# 04_Optical_Heads.net
KiCad netlist of a schematic drawn in Altium Designer
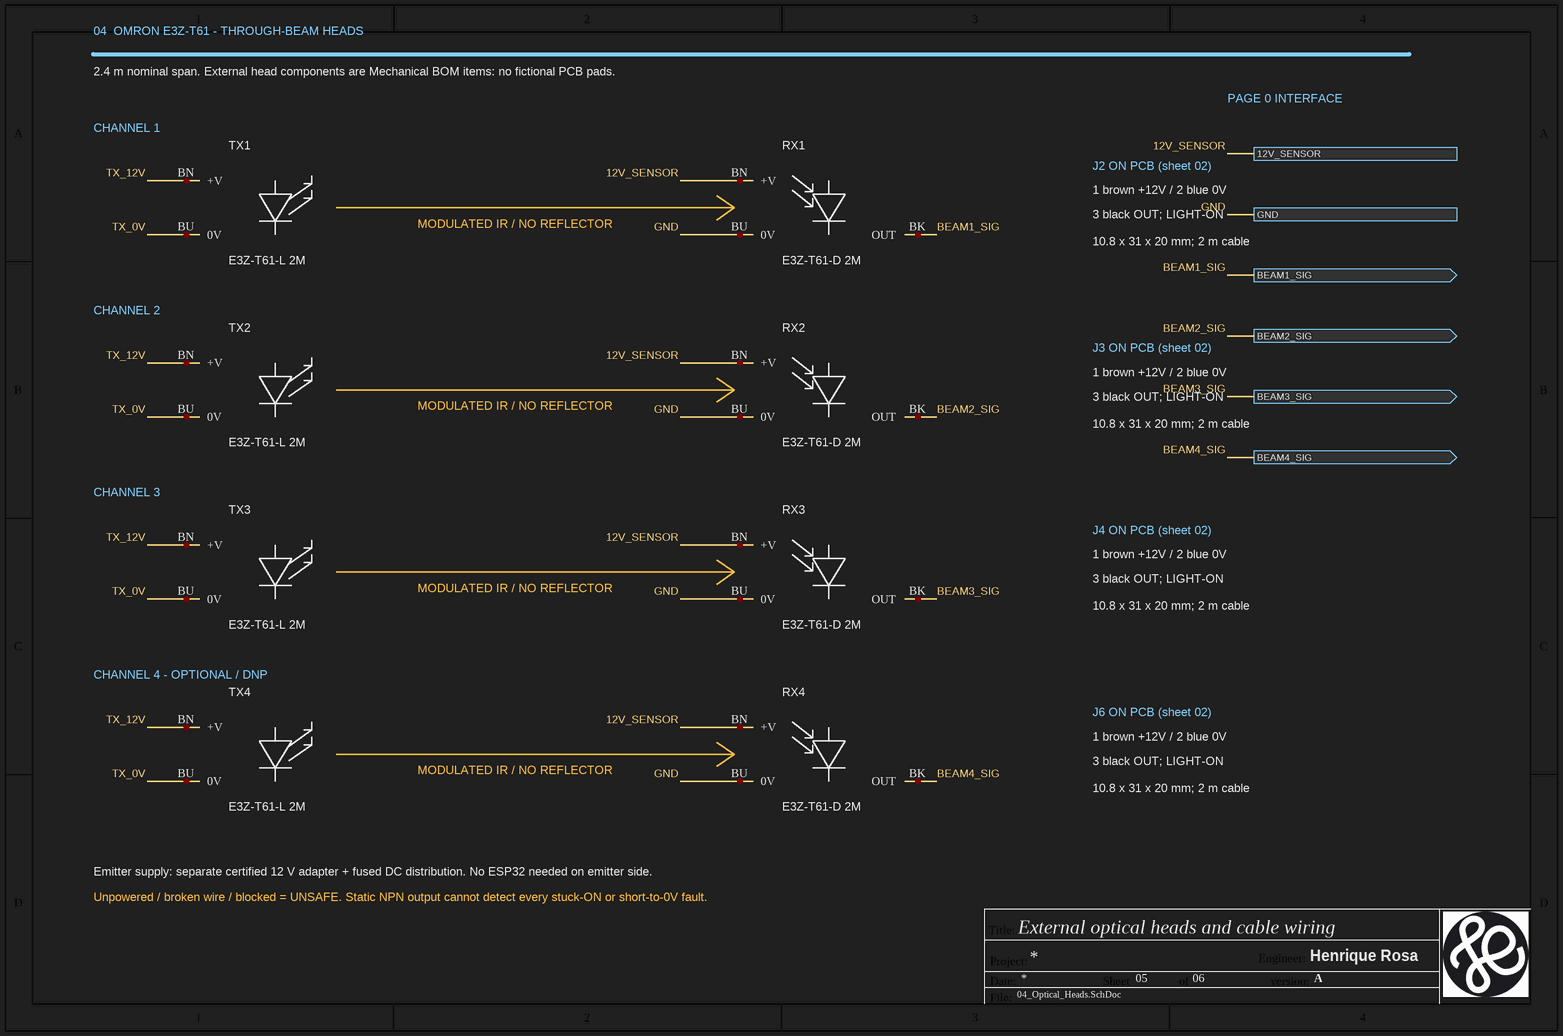
[diagram p0: 04_Optical_Heads.SchDoc]

(export (version "E")
  (design (tool "Eeschema 10.0.6"))
  (components
    (comp (ref "RX1")
      (value "E3Z-T61-D 2M")
      (description "RECEIVER / NPN LIGHT-ON; purchased in E3Z-T61 2M pair; frame-mounted, not PCB-mounted")
      (fields (field (name "MANUFACTURER") "Omron"))
      (libsource (lib "PartSpecificComponents") (part "OMRON_E3Z_T61_D_2M"))
    )
    (comp (ref "RX2")
      (value "E3Z-T61-D 2M")
      (description "RECEIVER / NPN LIGHT-ON; purchased in E3Z-T61 2M pair; frame-mounted, not PCB-mounted")
      (fields (field (name "MANUFACTURER") "Omron"))
      (libsource (lib "PartSpecificComponents") (part "OMRON_E3Z_T61_D_2M"))
    )
    (comp (ref "RX3")
      (value "E3Z-T61-D 2M")
      (description "RECEIVER / NPN LIGHT-ON; purchased in E3Z-T61 2M pair; frame-mounted, not PCB-mounted")
      (fields (field (name "MANUFACTURER") "Omron"))
      (libsource (lib "PartSpecificComponents") (part "OMRON_E3Z_T61_D_2M"))
    )
    (comp (ref "RX4")
      (value "E3Z-T61-D 2M")
      (description "RECEIVER / NPN LIGHT-ON; purchased in E3Z-T61 2M pair; frame-mounted, not PCB-mounted")
      (fields (field (name "MANUFACTURER") "Omron"))
      (libsource (lib "PartSpecificComponents") (part "OMRON_E3Z_T61_D_2M"))
    )
    (comp (ref "TX1")
      (value "E3Z-T61-L 2M")
      (description "EMITTER; purchased in E3Z-T61 2M pair; frame-mounted, not PCB-mounted")
      (fields (field (name "MANUFACTURER") "Omron"))
      (libsource (lib "PartSpecificComponents") (part "OMRON_E3Z_T61_L_2M"))
    )
    (comp (ref "TX2")
      (value "E3Z-T61-L 2M")
      (description "EMITTER; purchased in E3Z-T61 2M pair; frame-mounted, not PCB-mounted")
      (fields (field (name "MANUFACTURER") "Omron"))
      (libsource (lib "PartSpecificComponents") (part "OMRON_E3Z_T61_L_2M"))
    )
    (comp (ref "TX3")
      (value "E3Z-T61-L 2M")
      (description "EMITTER; purchased in E3Z-T61 2M pair; frame-mounted, not PCB-mounted")
      (fields (field (name "MANUFACTURER") "Omron"))
      (libsource (lib "PartSpecificComponents") (part "OMRON_E3Z_T61_L_2M"))
    )
    (comp (ref "TX4")
      (value "E3Z-T61-L 2M")
      (description "EMITTER; purchased in E3Z-T61 2M pair; frame-mounted, not PCB-mounted")
      (fields (field (name "MANUFACTURER") "Omron"))
      (libsource (lib "PartSpecificComponents") (part "OMRON_E3Z_T61_L_2M"))
    )
  )
  (nets
    (net (code "1") (name "/12V_SENSOR") (class "Default")
      (node (ref "RX1") (pin "BN") (pinfunction "+V_BN") (pintype "passive"))
      (node (ref "RX2") (pin "BN") (pinfunction "+V_BN") (pintype "passive"))
      (node (ref "RX3") (pin "BN") (pinfunction "+V_BN") (pintype "passive"))
      (node (ref "RX4") (pin "BN") (pinfunction "+V_BN") (pintype "passive"))
    )
    (net (code "2") (name "/BEAM1_SIG") (class "Default")
      (node (ref "RX1") (pin "BK") (pinfunction "OUT_BK") (pintype "passive"))
    )
    (net (code "3") (name "/BEAM2_SIG") (class "Default")
      (node (ref "RX2") (pin "BK") (pinfunction "OUT_BK") (pintype "passive"))
    )
    (net (code "4") (name "/BEAM3_SIG") (class "Default")
      (node (ref "RX3") (pin "BK") (pinfunction "OUT_BK") (pintype "passive"))
    )
    (net (code "5") (name "/BEAM4_SIG") (class "Default")
      (node (ref "RX4") (pin "BK") (pinfunction "OUT_BK") (pintype "passive"))
    )
    (net (code "6") (name "/GND") (class "Default")
      (node (ref "RX1") (pin "BU") (pinfunction "0V_BU") (pintype "passive"))
      (node (ref "RX2") (pin "BU") (pinfunction "0V_BU") (pintype "passive"))
      (node (ref "RX3") (pin "BU") (pinfunction "0V_BU") (pintype "passive"))
      (node (ref "RX4") (pin "BU") (pinfunction "0V_BU") (pintype "passive"))
    )
    (net (code "7") (name "/TX_0V") (class "Default")
      (node (ref "TX1") (pin "BU") (pinfunction "0V_BU") (pintype "passive"))
      (node (ref "TX2") (pin "BU") (pinfunction "0V_BU") (pintype "passive"))
      (node (ref "TX3") (pin "BU") (pinfunction "0V_BU") (pintype "passive"))
      (node (ref "TX4") (pin "BU") (pinfunction "0V_BU") (pintype "passive"))
    )
    (net (code "8") (name "/TX_12V") (class "Default")
      (node (ref "TX1") (pin "BN") (pinfunction "+V_BN") (pintype "passive"))
      (node (ref "TX2") (pin "BN") (pinfunction "+V_BN") (pintype "passive"))
      (node (ref "TX3") (pin "BN") (pinfunction "+V_BN") (pintype "passive"))
      (node (ref "TX4") (pin "BN") (pinfunction "+V_BN") (pintype "passive"))
    )
  )
)
